# MARK1_AUDIO_PMOD.net
KiCad netlist of a schematic drawn in Altium Designer
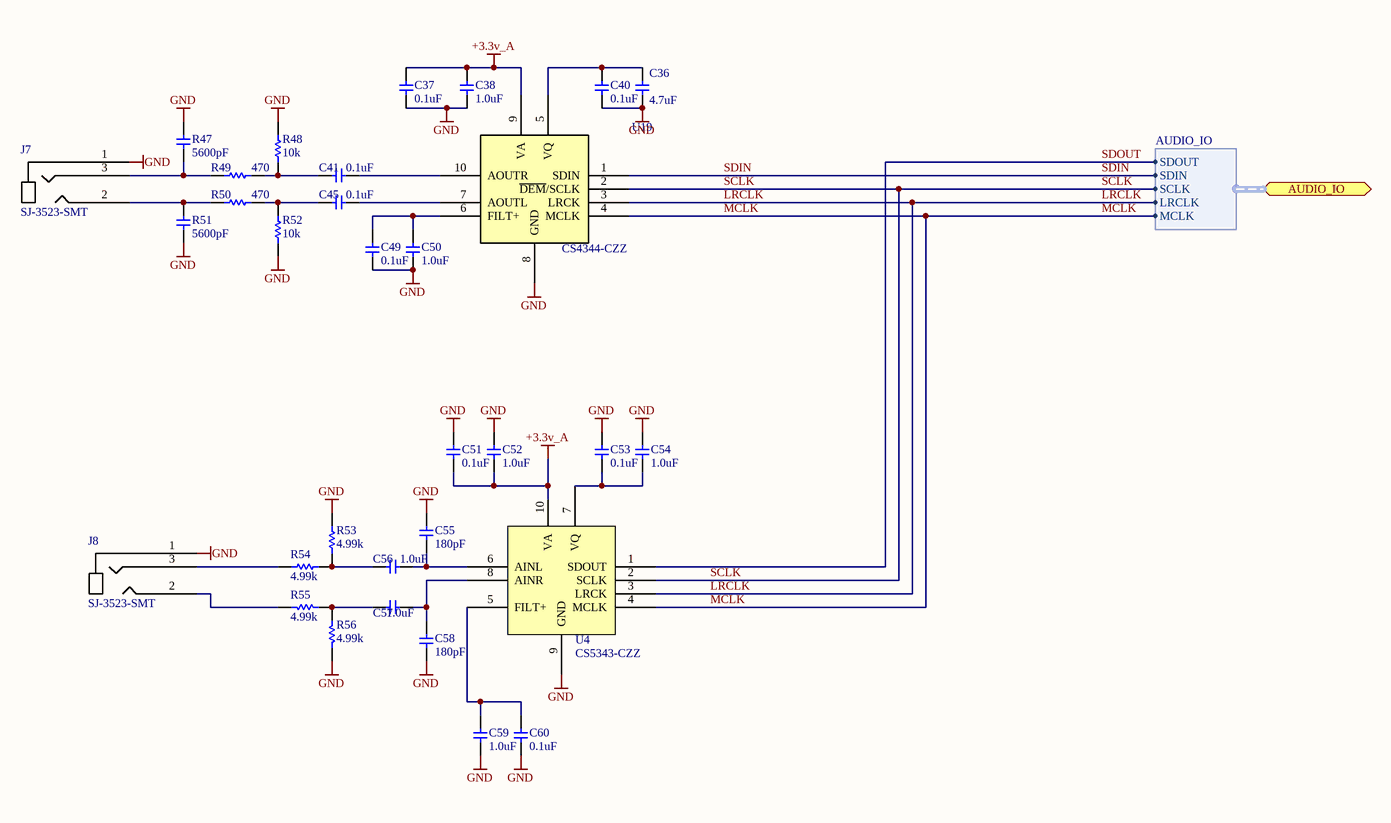
[diagram p0: MARK1_AUDIO_PMOD.SchDoc]

(export (version "E")
  (design (tool "Eeschema 10.0.6"))
  (components
    (comp (ref "C36")
      (value "4.7uF")
      (footprint "C0603")
      (description "CAP CER 4.7UF 6.3V X5R 0603")
      (fields
        (field (name "MANUFACTURER") "Murata Electronics North America")
        (field (name "MANUFACTURER PART NUMBER") "GRM188R60J475KE19D")
      )
      (libsource (lib "eCapacitors") (part "GRM188R60J475KE19D"))
    )
    (comp (ref "C37")
      (value "0.1uF")
      (footprint "C0603")
      (description "CAP CER .1UF 50V 10% X7R 0603")
      (fields
        (field (name "MANUFACTURER") "Murata Electronics North America")
        (field (name "MANUFACTURER PART NUMBER") "GRM188R71H104KA93D")
      )
      (libsource (lib "eCapacitors") (part "GRM188R71H104KA93D"))
    )
    (comp (ref "C38")
      (value "1.0uF")
      (footprint "C0805")
      (description "CAP CER 1.0UF 16V 10% X7R 0805")
      (fields
        (field (name "MANUFACTURER") "Murata Electronics North America")
        (field (name "MANUFACTURER PART NUMBER") "GRM21BR71C105KA01L")
      )
      (libsource (lib "eCapacitors") (part "GRM21BR71C105KA01L"))
    )
    (comp (ref "C40")
      (value "0.1uF")
      (footprint "C0603")
      (description "CAP CER .1UF 50V 10% X7R 0603")
      (fields
        (field (name "MANUFACTURER") "Murata Electronics North America")
        (field (name "MANUFACTURER PART NUMBER") "GRM188R71H104KA93D")
      )
      (libsource (lib "eCapacitors") (part "GRM188R71H104KA93D"))
    )
    (comp (ref "C41")
      (value "0.1uF")
      (footprint "C0603")
      (description "CAP CER .1UF 50V 10% X7R 0603")
      (fields
        (field (name "MANUFACTURER") "Murata Electronics North America")
        (field (name "MANUFACTURER PART NUMBER") "GRM188R71H104KA93D")
      )
      (libsource (lib "eCapacitors") (part "GRM188R71H104KA93D"))
    )
    (comp (ref "C45")
      (value "0.1uF")
      (footprint "C0603")
      (description "CAP CER .1UF 50V 10% X7R 0603")
      (fields
        (field (name "MANUFACTURER") "Murata Electronics North America")
        (field (name "MANUFACTURER PART NUMBER") "GRM188R71H104KA93D")
      )
      (libsource (lib "eCapacitors") (part "GRM188R71H104KA93D"))
    )
    (comp (ref "C49")
      (value "0.1uF")
      (footprint "C0603")
      (description "CAP CER .1UF 50V 10% X7R 0603")
      (fields
        (field (name "MANUFACTURER") "Murata Electronics North America")
        (field (name "MANUFACTURER PART NUMBER") "GRM188R71H104KA93D")
      )
      (libsource (lib "eCapacitors") (part "GRM188R71H104KA93D"))
    )
    (comp (ref "C50")
      (value "1.0uF")
      (footprint "C0805")
      (description "CAP CER 1.0UF 16V 10% X7R 0805")
      (fields
        (field (name "MANUFACTURER") "Murata Electronics North America")
        (field (name "MANUFACTURER PART NUMBER") "GRM21BR71C105KA01L")
      )
      (libsource (lib "eCapacitors") (part "GRM21BR71C105KA01L"))
    )
    (comp (ref "C51")
      (value "0.1uF")
      (footprint "C0603")
      (description "CAP CER .1UF 50V 10% X7R 0603")
      (fields
        (field (name "MANUFACTURER") "Murata Electronics North America")
        (field (name "MANUFACTURER PART NUMBER") "GRM188R71H104KA93D")
      )
      (libsource (lib "eCapacitors") (part "GRM188R71H104KA93D"))
    )
    (comp (ref "C52")
      (value "1.0uF")
      (footprint "C0805")
      (description "CAP CER 1.0UF 16V 10% X7R 0805")
      (fields
        (field (name "MANUFACTURER") "Murata Electronics North America")
        (field (name "MANUFACTURER PART NUMBER") "GRM21BR71C105KA01L")
      )
      (libsource (lib "eCapacitors") (part "GRM21BR71C105KA01L"))
    )
    (comp (ref "C53")
      (value "0.1uF")
      (footprint "C0603")
      (description "CAP CER .1UF 50V 10% X7R 0603")
      (fields
        (field (name "MANUFACTURER") "Murata Electronics North America")
        (field (name "MANUFACTURER PART NUMBER") "GRM188R71H104KA93D")
      )
      (libsource (lib "eCapacitors") (part "GRM188R71H104KA93D"))
    )
    (comp (ref "C54")
      (value "1.0uF")
      (footprint "C0805")
      (description "CAP CER 1.0UF 16V 10% X7R 0805")
      (fields
        (field (name "MANUFACTURER") "Murata Electronics North America")
        (field (name "MANUFACTURER PART NUMBER") "GRM21BR71C105KA01L")
      )
      (libsource (lib "eCapacitors") (part "GRM21BR71C105KA01L"))
    )
    (comp (ref "C55")
      (value "180pF")
      (footprint "C0603")
      (description "CAP CER 180PF 50V 5% NP0 0603")
      (fields
        (field (name "MANUFACTURER") "TDK Corporation")
        (field (name "MANUFACTURER PART NUMBER") "C1608C0G1H181J")
      )
      (libsource (lib "eCapacitors") (part "C1608C0G1H181J"))
    )
    (comp (ref "C56")
      (value "1.0uF")
      (footprint "C0805")
      (description "CAP CER 1.0UF 16V 10% X7R 0805")
      (fields
        (field (name "MANUFACTURER") "Murata Electronics North America")
        (field (name "MANUFACTURER PART NUMBER") "GRM21BR71C105KA01L")
      )
      (libsource (lib "eCapacitors") (part "GRM21BR71C105KA01L"))
    )
    (comp (ref "C57")
      (value "1.0uF")
      (footprint "C0805")
      (description "CAP CER 1.0UF 16V 10% X7R 0805")
      (fields
        (field (name "MANUFACTURER") "Murata Electronics North America")
        (field (name "MANUFACTURER PART NUMBER") "GRM21BR71C105KA01L")
      )
      (libsource (lib "eCapacitors") (part "GRM21BR71C105KA01L"))
    )
    (comp (ref "C58")
      (value "180pF")
      (footprint "C0603")
      (description "CAP CER 180PF 50V 5% NP0 0603")
      (fields
        (field (name "MANUFACTURER") "TDK Corporation")
        (field (name "MANUFACTURER PART NUMBER") "C1608C0G1H181J")
      )
      (libsource (lib "eCapacitors") (part "C1608C0G1H181J"))
    )
    (comp (ref "C59")
      (value "1.0uF")
      (footprint "C0805")
      (description "CAP CER 1.0UF 16V 10% X7R 0805")
      (fields
        (field (name "MANUFACTURER") "Murata Electronics North America")
        (field (name "MANUFACTURER PART NUMBER") "GRM21BR71C105KA01L")
      )
      (libsource (lib "eCapacitors") (part "GRM21BR71C105KA01L"))
    )
    (comp (ref "C60")
      (value "0.1uF")
      (footprint "C0603")
      (description "CAP CER .1UF 50V 10% X7R 0603")
      (fields
        (field (name "MANUFACTURER") "Murata Electronics North America")
        (field (name "MANUFACTURER PART NUMBER") "GRM188R71H104KA93D")
      )
      (libsource (lib "eCapacitors") (part "GRM188R71H104KA93D"))
    )
    (comp (ref "J7")
      (value "SJ-3523-SMT")
      (footprint "SJ-3523-SMT")
      (description "CONN AUDIO JACK 3.5MM STEREO SMD")
      (fields (field (name "MANUFACTURER") "CUI Inc") (field (name "SOURCE") "Digikey"))
      (libsource (lib "eConnector") (part "SJ-3523-SMT"))
    )
    (comp (ref "J8")
      (value "SJ-3523-SMT")
      (footprint "SJ-3523-SMT")
      (description "CONN AUDIO JACK 3.5MM STEREO SMD")
      (fields (field (name "MANUFACTURER") "CUI Inc") (field (name "SOURCE") "Digikey"))
      (libsource (lib "eConnector") (part "SJ-3523-SMT"))
    )
    (comp (ref "R47")
      (value "5600pF")
      (footprint "C0603")
      (description "CAP CER 5600PF 50V 10% X7R 0603")
      (fields
        (field (name "MANUFACTURER") "Murata Electronics North America")
        (field (name "MANUFACTURER PART NUMBER") "GRM188R71H562KA01D")
      )
      (libsource (lib "eCapacitors") (part "GRM188R71H562KA01D"))
    )
    (comp (ref "R48")
      (value "10k")
      (footprint "R0603")
      (description "RES 10.0K OHM 1/10W 1% 0603 SMD")
      (fields
        (field (name "MANUFACTURER") "Panasonic - ECG")
        (field (name "TOLERANCE") "±1%")
        (field (name "SOURCE") "Digikey")
      )
      (libsource (lib "eRCL") (part "ERJ-3EKF1002V"))
    )
    (comp (ref "R49")
      (value "470")
      (footprint "R0603")
      (description "RES 470 OHM 1/10W 1% 0603 SMD")
      (fields
        (field (name "MANUFACTURER") "Panasonic - ECG")
        (field (name "MANUFACTURER PART NUMBER") "ERJ-3EKF4700V")
      )
      (libsource (lib "eResistors") (part "ERJ-3EKF4700V"))
    )
    (comp (ref "R50")
      (value "470")
      (footprint "R0603")
      (description "RES 470 OHM 1/10W 1% 0603 SMD")
      (fields
        (field (name "MANUFACTURER") "Panasonic - ECG")
        (field (name "MANUFACTURER PART NUMBER") "ERJ-3EKF4700V")
      )
      (libsource (lib "eResistors") (part "ERJ-3EKF4700V"))
    )
    (comp (ref "R51")
      (value "5600pF")
      (footprint "C0603")
      (description "CAP CER 5600PF 50V 10% X7R 0603")
      (fields
        (field (name "MANUFACTURER") "Murata Electronics North America")
        (field (name "MANUFACTURER PART NUMBER") "GRM188R71H562KA01D")
      )
      (libsource (lib "eCapacitors") (part "GRM188R71H562KA01D"))
    )
    (comp (ref "R52")
      (value "10k")
      (footprint "R0603")
      (description "RES 10.0K OHM 1/10W 1% 0603 SMD")
      (fields
        (field (name "MANUFACTURER") "Panasonic - ECG")
        (field (name "TOLERANCE") "±1%")
        (field (name "SOURCE") "Digikey")
      )
      (libsource (lib "eRCL") (part "ERJ-3EKF1002V"))
    )
    (comp (ref "R53")
      (value "4.99k")
      (footprint "R0603")
      (description "RES 4.99K OHM 1/10W 1% 0603 SMD")
      (fields
        (field (name "MANUFACTURER") "Panasonic - ECG")
        (field (name "MANUFACTURER PART NUMBER") "ERJ-3EKF4991V")
      )
      (libsource (lib "eResistors") (part "ERJ-3EKF4991V"))
    )
    (comp (ref "R54")
      (value "4.99k")
      (footprint "R0603")
      (description "RES 4.99K OHM 1/10W 1% 0603 SMD")
      (fields
        (field (name "MANUFACTURER") "Panasonic - ECG")
        (field (name "MANUFACTURER PART NUMBER") "ERJ-3EKF4991V")
      )
      (libsource (lib "eResistors") (part "ERJ-3EKF4991V"))
    )
    (comp (ref "R55")
      (value "4.99k")
      (footprint "R0603")
      (description "RES 4.99K OHM 1/10W 1% 0603 SMD")
      (fields
        (field (name "MANUFACTURER") "Panasonic - ECG")
        (field (name "MANUFACTURER PART NUMBER") "ERJ-3EKF4991V")
      )
      (libsource (lib "eResistors") (part "ERJ-3EKF4991V"))
    )
    (comp (ref "R56")
      (value "4.99k")
      (footprint "R0603")
      (description "RES 4.99K OHM 1/10W 1% 0603 SMD")
      (fields
        (field (name "MANUFACTURER") "Panasonic - ECG")
        (field (name "MANUFACTURER PART NUMBER") "ERJ-3EKF4991V")
      )
      (libsource (lib "eResistors") (part "ERJ-3EKF4991V"))
    )
    (comp (ref "U4")
      (value "CS5343-CZZ")
      (footprint "TSSOP10")
      (description "IC ADC AUD 98DB 108KHZ 10-TSSOP")
      (fields (field (name "MANUFACTURER") "rus Logic Inc") (field (name "SOURCE") "Digikey"))
      (libsource (lib "EE417") (part "CS5343-CZZ"))
    )
    (comp (ref "U19")
      (value "CS4344-CZZ")
      (footprint "TSSOP10")
      (description "IC DAC STER 24BIT 192KHZ 10TSSOP")
      (fields (field (name "MANUFACTURER") "rus Logic Inc") (field (name "SOURCE") "Digikey"))
      (libsource (lib "eIC") (part "CS4344-CZZ"))
    )
  )
  (nets
    (net (code "2") (name "+3.3v_A") (class "Default")
      (node (ref "C37") (pin "2") (pinfunction "2_2") (pintype "passive"))
      (node (ref "C38") (pin "2") (pinfunction "2_2") (pintype "passive"))
      (node (ref "C51") (pin "1") (pinfunction "1_1") (pintype "passive"))
      (node (ref "C52") (pin "1") (pinfunction "1_1") (pintype "passive"))
      (node (ref "U19") (pin "9") (pinfunction "VA_9") (pintype "passive"))
      (node (ref "U4") (pin "10") (pinfunction "VA_10") (pintype "passive"))
    )
    (net (code "3") (name "/LRCLK") (class "Default")
      (node (ref "U19") (pin "3") (pinfunction "LRCK_3") (pintype "passive"))
      (node (ref "U4") (pin "3") (pinfunction "LRCK_3") (pintype "passive"))
    )
    (net (code "4") (name "/MCLK") (class "Default")
      (node (ref "U19") (pin "4") (pinfunction "MCLK_4") (pintype "passive"))
      (node (ref "U4") (pin "4") (pinfunction "MCLK_4") (pintype "passive"))
    )
    (net (code "5") (name "/SCLK") (class "Default")
      (node (ref "U19") (pin "2") (pinfunction "~{DEM}/SCLK_2") (pintype "passive"))
      (node (ref "U4") (pin "2") (pinfunction "SCLK_2") (pintype "passive"))
    )
    (net (code "6") (name "/SDIN") (class "Default")
      (node (ref "U19") (pin "1") (pinfunction "SDIN_1") (pintype "passive"))
    )
    (net (code "7") (name "/SDOUT") (class "Default")
      (node (ref "U4") (pin "1") (pinfunction "SDOUT_1") (pintype "passive"))
    )
    (net (code "9") (name "GND") (class "Default")
      (node (ref "C36") (pin "1") (pinfunction "1_1") (pintype "passive"))
      (node (ref "C37") (pin "1") (pinfunction "1_1") (pintype "passive"))
      (node (ref "C38") (pin "1") (pinfunction "1_1") (pintype "passive"))
      (node (ref "C40") (pin "1") (pinfunction "1_1") (pintype "passive"))
      (node (ref "C49") (pin "1") (pinfunction "1_1") (pintype "passive"))
      (node (ref "C50") (pin "1") (pinfunction "1_1") (pintype "passive"))
      (node (ref "C51") (pin "2") (pinfunction "2_2") (pintype "passive"))
      (node (ref "C52") (pin "2") (pinfunction "2_2") (pintype "passive"))
      (node (ref "C53") (pin "2") (pinfunction "2_2") (pintype "passive"))
      (node (ref "C54") (pin "2") (pinfunction "2_2") (pintype "passive"))
      (node (ref "C55") (pin "2") (pinfunction "2_2") (pintype "passive"))
      (node (ref "C58") (pin "1") (pinfunction "1_1") (pintype "passive"))
      (node (ref "C59") (pin "2") (pinfunction "2_2") (pintype "passive"))
      (node (ref "C60") (pin "2") (pinfunction "2_2") (pintype "passive"))
      (node (ref "J7") (pin "1") (pinfunction "1_1") (pintype "passive"))
      (node (ref "J8") (pin "1") (pinfunction "1_1") (pintype "passive"))
      (node (ref "R47") (pin "2") (pinfunction "2_2") (pintype "passive"))
      (node (ref "R48") (pin "1") (pinfunction "1_1") (pintype "passive"))
      (node (ref "R51") (pin "1") (pinfunction "1_1") (pintype "passive"))
      (node (ref "R52") (pin "2") (pinfunction "2_2") (pintype "passive"))
      (node (ref "R53") (pin "2") (pinfunction "2_2") (pintype "passive"))
      (node (ref "R56") (pin "2") (pinfunction "2_2") (pintype "passive"))
      (node (ref "U19") (pin "8") (pinfunction "GND_8") (pintype "passive"))
      (node (ref "U4") (pin "9") (pinfunction "GND_9") (pintype "passive"))
    )
    (net (code "10") (name "Net-(C41-Pad2)") (class "Default")
      (node (ref "C41") (pin "2") (pinfunction "2_2") (pintype "passive"))
      (node (ref "R48") (pin "2") (pinfunction "2_2") (pintype "passive"))
      (node (ref "R49") (pin "1") (pinfunction "1_1") (pintype "passive"))
    )
    (net (code "11") (name "Net-(C45-Pad2)") (class "Default")
      (node (ref "C45") (pin "2") (pinfunction "2_2") (pintype "passive"))
      (node (ref "R50") (pin "1") (pinfunction "1_1") (pintype "passive"))
      (node (ref "R52") (pin "1") (pinfunction "1_1") (pintype "passive"))
    )
    (net (code "12") (name "Net-(C56-Pad1)") (class "Default")
      (node (ref "C56") (pin "1") (pinfunction "1_1") (pintype "passive"))
      (node (ref "R53") (pin "1") (pinfunction "1_1") (pintype "passive"))
      (node (ref "R54") (pin "2") (pinfunction "2_2") (pintype "passive"))
    )
    (net (code "13") (name "Net-(C57-Pad1)") (class "Default")
      (node (ref "C57") (pin "1") (pinfunction "1_1") (pintype "passive"))
      (node (ref "R55") (pin "2") (pinfunction "2_2") (pintype "passive"))
      (node (ref "R56") (pin "1") (pinfunction "1_1") (pintype "passive"))
    )
    (net (code "14") (name "Net-(J7-Pad2)") (class "Default")
      (node (ref "J7") (pin "2") (pinfunction "2_2") (pintype "passive"))
      (node (ref "R50") (pin "2") (pinfunction "2_2") (pintype "passive"))
      (node (ref "R51") (pin "2") (pinfunction "2_2") (pintype "passive"))
    )
    (net (code "15") (name "Net-(J7-Pad3)") (class "Default")
      (node (ref "J7") (pin "3") (pinfunction "3_3") (pintype "passive"))
      (node (ref "R47") (pin "1") (pinfunction "1_1") (pintype "passive"))
      (node (ref "R49") (pin "2") (pinfunction "2_2") (pintype "passive"))
    )
    (net (code "16") (name "Net-(J8-Pad2)") (class "Default")
      (node (ref "J8") (pin "2") (pinfunction "2_2") (pintype "passive"))
      (node (ref "R55") (pin "1") (pinfunction "1_1") (pintype "passive"))
    )
    (net (code "17") (name "Net-(J8-Pad3)") (class "Default")
      (node (ref "J8") (pin "3") (pinfunction "3_3") (pintype "passive"))
      (node (ref "R54") (pin "1") (pinfunction "1_1") (pintype "passive"))
    )
    (net (code "18") (name "Net-(U4-AINL)") (class "Default")
      (node (ref "C55") (pin "1") (pinfunction "1_1") (pintype "passive"))
      (node (ref "C56") (pin "2") (pinfunction "2_2") (pintype "passive"))
      (node (ref "U4") (pin "6") (pinfunction "AINL_6") (pintype "passive"))
    )
    (net (code "19") (name "Net-(U4-AINR)") (class "Default")
      (node (ref "C57") (pin "2") (pinfunction "2_2") (pintype "passive"))
      (node (ref "C58") (pin "2") (pinfunction "2_2") (pintype "passive"))
      (node (ref "U4") (pin "8") (pinfunction "AINR_8") (pintype "passive"))
    )
    (net (code "20") (name "Net-(U4-FILT+)") (class "Default")
      (node (ref "C59") (pin "1") (pinfunction "1_1") (pintype "passive"))
      (node (ref "C60") (pin "1") (pinfunction "1_1") (pintype "passive"))
      (node (ref "U4") (pin "5") (pinfunction "FILT+_5") (pintype "passive"))
    )
    (net (code "21") (name "Net-(U4-VQ)") (class "Default")
      (node (ref "C53") (pin "1") (pinfunction "1_1") (pintype "passive"))
      (node (ref "C54") (pin "1") (pinfunction "1_1") (pintype "passive"))
      (node (ref "U4") (pin "7") (pinfunction "VQ_7") (pintype "passive"))
    )
    (net (code "22") (name "Net-(U19-AOUTL)") (class "Default")
      (node (ref "C45") (pin "1") (pinfunction "1_1") (pintype "passive"))
      (node (ref "U19") (pin "7") (pinfunction "AOUTL_7") (pintype "passive"))
    )
    (net (code "23") (name "Net-(U19-AOUTR)") (class "Default")
      (node (ref "C41") (pin "1") (pinfunction "1_1") (pintype "passive"))
      (node (ref "U19") (pin "10") (pinfunction "AOUTR_10") (pintype "passive"))
    )
    (net (code "24") (name "Net-(U19-FILT+)") (class "Default")
      (node (ref "C49") (pin "2") (pinfunction "2_2") (pintype "passive"))
      (node (ref "C50") (pin "2") (pinfunction "2_2") (pintype "passive"))
      (node (ref "U19") (pin "6") (pinfunction "FILT+_6") (pintype "passive"))
    )
    (net (code "25") (name "Net-(U19-VQ)") (class "Default")
      (node (ref "C36") (pin "2") (pinfunction "2_2") (pintype "passive"))
      (node (ref "C40") (pin "2") (pinfunction "2_2") (pintype "passive"))
      (node (ref "U19") (pin "5") (pinfunction "VQ_5") (pintype "passive"))
    )
  )
)
